# driver.net
KiCad netlist of a schematic drawn in EAGLE
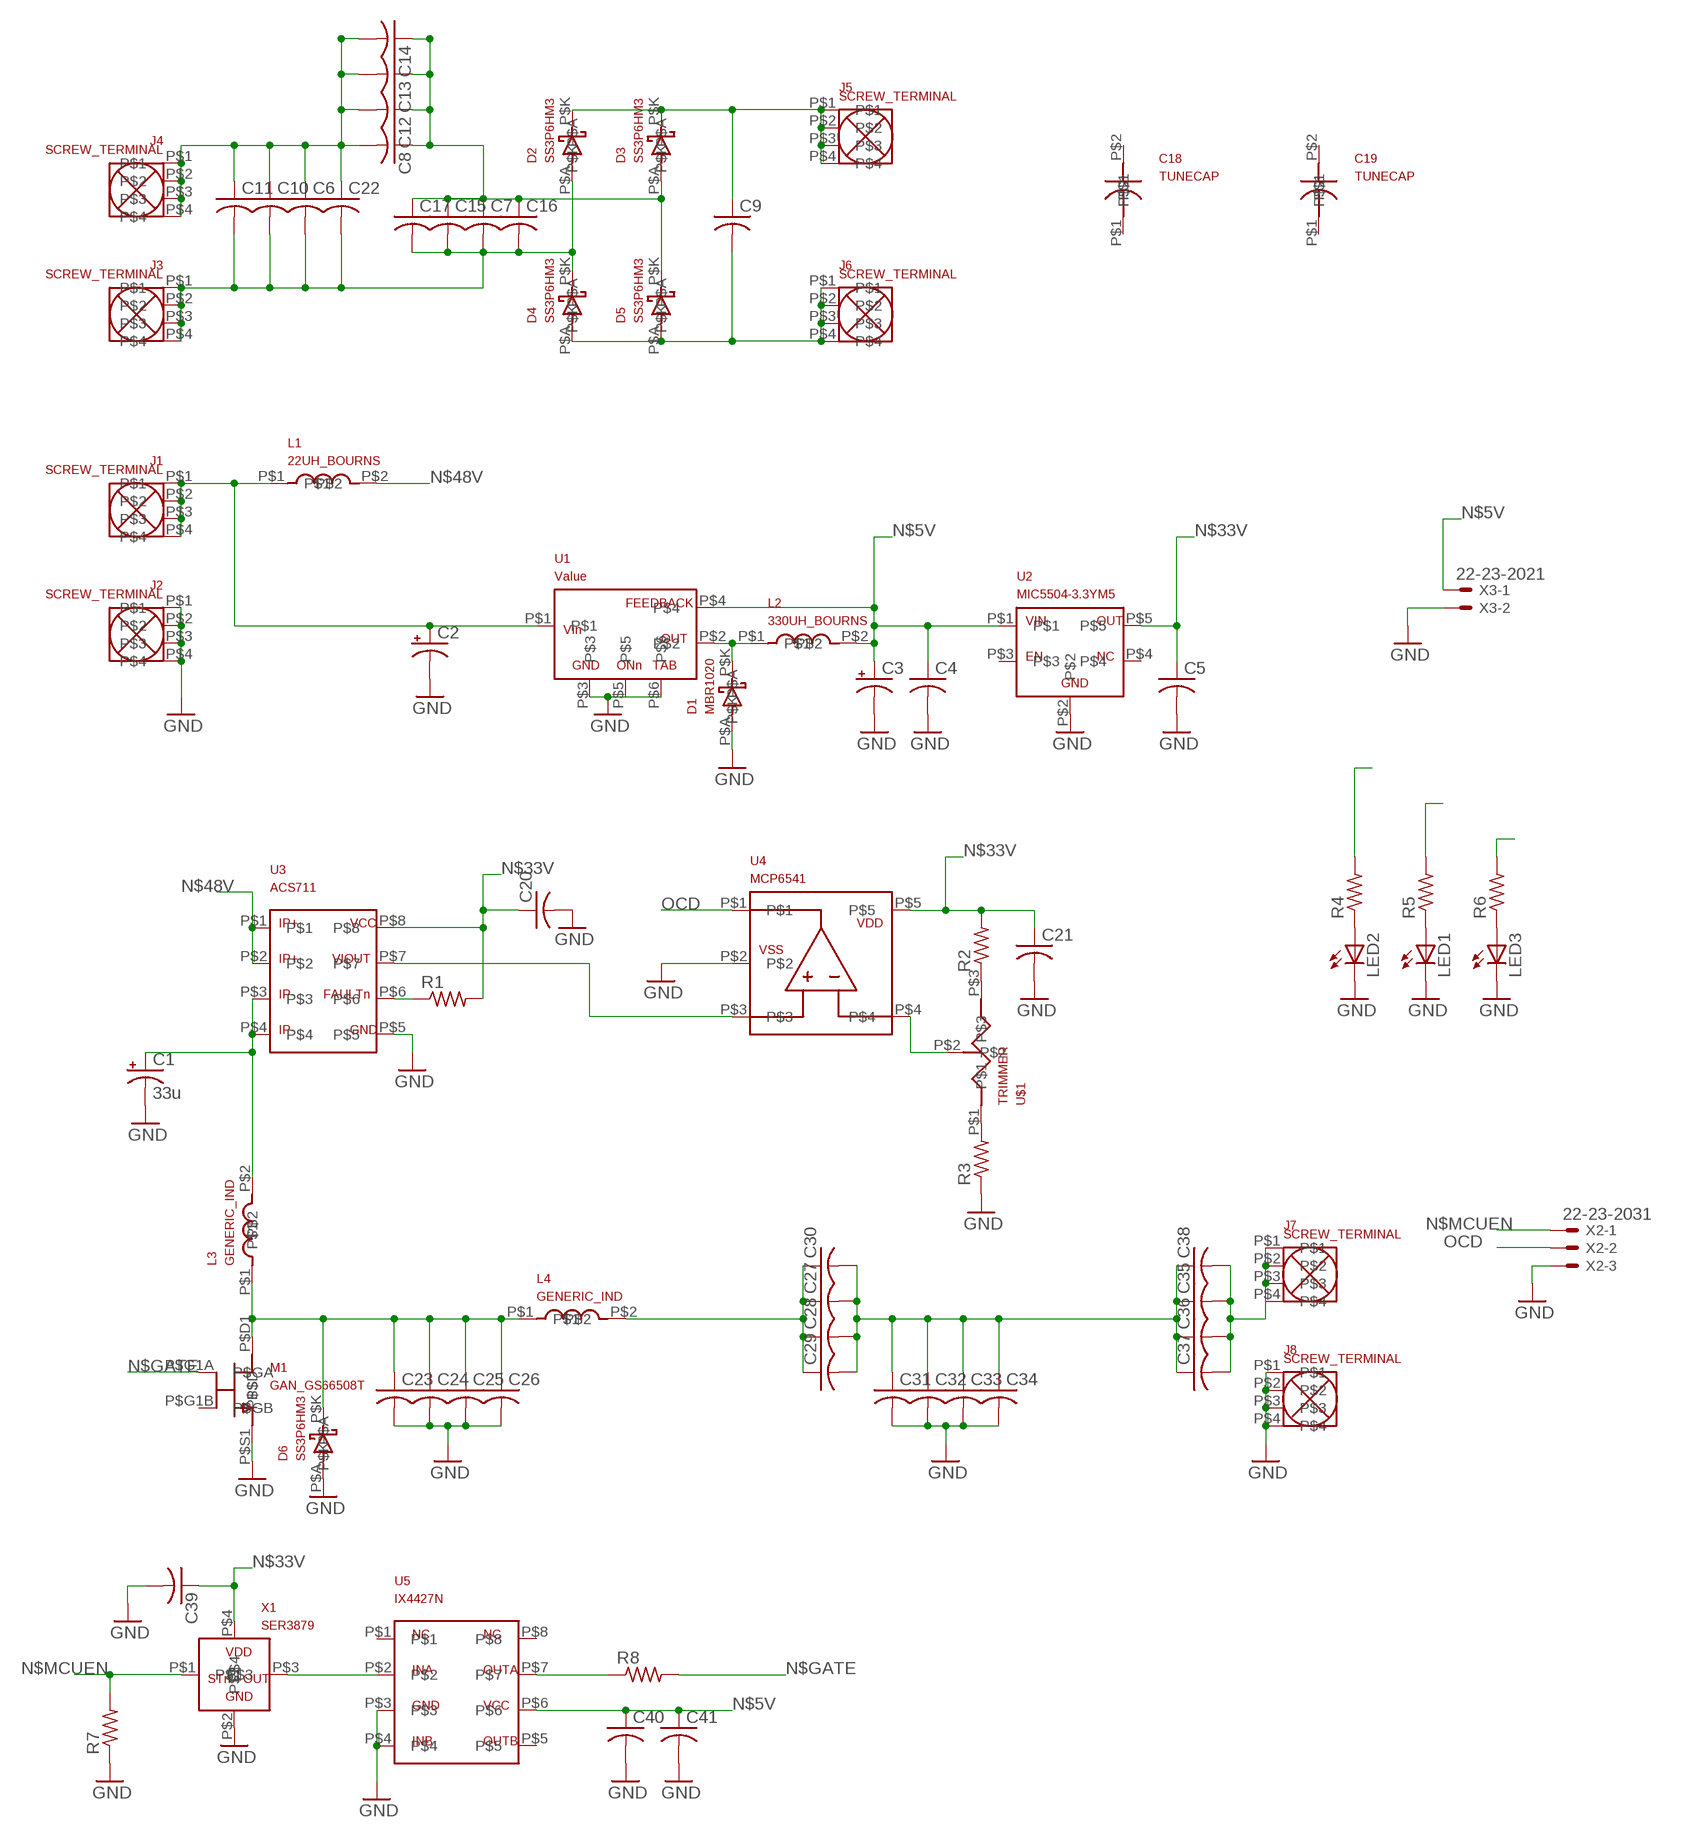
[diagram p0: schematic, sheet 1]

(export (version "E")
  (design (tool "Eeschema 10.0.6"))
  (components
    (comp (ref "C1")
      (value "33u")
      (footprint "eagle-import:140CLH-0810")
      (libsource (lib "eagle-import") (part "CPOL-US140CLH-0810"))
    )
    (comp (ref "C2")
      (value "CPOL-US140CLH-1010")
      (footprint "eagle-import:140CLH-1010")
      (libsource (lib "eagle-import") (part "CPOL-US140CLH-1010"))
    )
    (comp (ref "C3")
      (value "CPOL-US150CLZ-0810")
      (footprint "eagle-import:150CLZ-0810")
      (libsource (lib "eagle-import") (part "CPOL-US150CLZ-0810"))
    )
    (comp (ref "C4")
      (value "C-USC0603K")
      (footprint "eagle-import:C0603K")
      (libsource (lib "eagle-import") (part "C-USC0603K"))
    )
    (comp (ref "C5")
      (value "C-USC0603K")
      (footprint "eagle-import:C0603K")
      (libsource (lib "eagle-import") (part "C-USC0603K"))
    )
    (comp (ref "C6")
      (value "C-USC1206K")
      (footprint "eagle-import:C1206K")
      (libsource (lib "eagle-import") (part "C-USC1206K"))
    )
    (comp (ref "C7")
      (value "C-USC1206K")
      (footprint "eagle-import:C1206K")
      (libsource (lib "eagle-import") (part "C-USC1206K"))
    )
    (comp (ref "C8")
      (value "C-USC1206K")
      (footprint "eagle-import:C1206K")
      (libsource (lib "eagle-import") (part "C-USC1206K"))
    )
    (comp (ref "C9")
      (value "C-USC1206K")
      (footprint "eagle-import:C1206K")
      (libsource (lib "eagle-import") (part "C-USC1206K"))
    )
    (comp (ref "C10")
      (value "C-USC1206K")
      (footprint "eagle-import:C1206K")
      (libsource (lib "eagle-import") (part "C-USC1206K"))
    )
    (comp (ref "C11")
      (value "C-USC1206K")
      (footprint "eagle-import:C1206K")
      (libsource (lib "eagle-import") (part "C-USC1206K"))
    )
    (comp (ref "C12")
      (value "C-USC1206K")
      (footprint "eagle-import:C1206K")
      (libsource (lib "eagle-import") (part "C-USC1206K"))
    )
    (comp (ref "C13")
      (value "C-USC1206K")
      (footprint "eagle-import:C1206K")
      (libsource (lib "eagle-import") (part "C-USC1206K"))
    )
    (comp (ref "C14")
      (value "C-USC1206K")
      (footprint "eagle-import:C1206K")
      (libsource (lib "eagle-import") (part "C-USC1206K"))
    )
    (comp (ref "C15")
      (value "C-USC1206K")
      (footprint "eagle-import:C1206K")
      (libsource (lib "eagle-import") (part "C-USC1206K"))
    )
    (comp (ref "C16")
      (value "C-USC1206K")
      (footprint "eagle-import:C1206K")
      (libsource (lib "eagle-import") (part "C-USC1206K"))
    )
    (comp (ref "C17")
      (value "C-USC1206K")
      (footprint "eagle-import:C1206K")
      (libsource (lib "eagle-import") (part "C-USC1206K"))
    )
    (comp (ref "C18")
      (value "TUNECAP")
      (footprint "eagle-import:CAPTUNE")
      (libsource (lib "eagle-import") (part "TUNECAP"))
    )
    (comp (ref "C19")
      (value "TUNECAP")
      (footprint "eagle-import:CAPTUNE")
      (libsource (lib "eagle-import") (part "TUNECAP"))
    )
    (comp (ref "C20")
      (value "C-USC0603")
      (footprint "eagle-import:C0603")
      (libsource (lib "eagle-import") (part "C-USC0603"))
    )
    (comp (ref "C21")
      (value "C-USC0603K")
      (footprint "eagle-import:C0603K")
      (libsource (lib "eagle-import") (part "C-USC0603K"))
    )
    (comp (ref "C22")
      (value "C-USC1206K")
      (footprint "eagle-import:C1206K")
      (libsource (lib "eagle-import") (part "C-USC1206K"))
    )
    (comp (ref "C23")
      (value "C-USC1206K")
      (footprint "eagle-import:C1206K")
      (libsource (lib "eagle-import") (part "C-USC1206K"))
    )
    (comp (ref "C24")
      (value "C-USC1206K")
      (footprint "eagle-import:C1206K")
      (libsource (lib "eagle-import") (part "C-USC1206K"))
    )
    (comp (ref "C25")
      (value "C-USC1206K")
      (footprint "eagle-import:C1206K")
      (libsource (lib "eagle-import") (part "C-USC1206K"))
    )
    (comp (ref "C26")
      (value "C-USC1206K")
      (footprint "eagle-import:C1206K")
      (libsource (lib "eagle-import") (part "C-USC1206K"))
    )
    (comp (ref "C27")
      (value "C-USC1206K")
      (footprint "eagle-import:C1206K")
      (libsource (lib "eagle-import") (part "C-USC1206K"))
    )
    (comp (ref "C28")
      (value "C-USC1206K")
      (footprint "eagle-import:C1206K")
      (libsource (lib "eagle-import") (part "C-USC1206K"))
    )
    (comp (ref "C29")
      (value "C-USC1206K")
      (footprint "eagle-import:C1206K")
      (libsource (lib "eagle-import") (part "C-USC1206K"))
    )
    (comp (ref "C30")
      (value "C-USC1206K")
      (footprint "eagle-import:C1206K")
      (libsource (lib "eagle-import") (part "C-USC1206K"))
    )
    (comp (ref "C31")
      (value "C-USC1206K")
      (footprint "eagle-import:C1206K")
      (libsource (lib "eagle-import") (part "C-USC1206K"))
    )
    (comp (ref "C32")
      (value "C-USC1206K")
      (footprint "eagle-import:C1206K")
      (libsource (lib "eagle-import") (part "C-USC1206K"))
    )
    (comp (ref "C33")
      (value "C-USC1206K")
      (footprint "eagle-import:C1206K")
      (libsource (lib "eagle-import") (part "C-USC1206K"))
    )
    (comp (ref "C34")
      (value "C-USC1206K")
      (footprint "eagle-import:C1206K")
      (libsource (lib "eagle-import") (part "C-USC1206K"))
    )
    (comp (ref "C35")
      (value "C-USC1206K")
      (footprint "eagle-import:C1206K")
      (libsource (lib "eagle-import") (part "C-USC1206K"))
    )
    (comp (ref "C36")
      (value "C-USC1206K")
      (footprint "eagle-import:C1206K")
      (libsource (lib "eagle-import") (part "C-USC1206K"))
    )
    (comp (ref "C37")
      (value "C-USC1206K")
      (footprint "eagle-import:C1206K")
      (libsource (lib "eagle-import") (part "C-USC1206K"))
    )
    (comp (ref "C38")
      (value "C-USC1206K")
      (footprint "eagle-import:C1206K")
      (libsource (lib "eagle-import") (part "C-USC1206K"))
    )
    (comp (ref "C39")
      (value "C-USC0603K")
      (footprint "eagle-import:C0603K")
      (libsource (lib "eagle-import") (part "C-USC0603K"))
    )
    (comp (ref "C40")
      (value "C-USC0603K")
      (footprint "eagle-import:C0603K")
      (libsource (lib "eagle-import") (part "C-USC0603K"))
    )
    (comp (ref "C41")
      (value "C-USC0603K")
      (footprint "eagle-import:C0603K")
      (libsource (lib "eagle-import") (part "C-USC0603K"))
    )
    (comp (ref "D1")
      (value "MBR1020")
      (footprint "eagle-import:SOD-123")
      (libsource (lib "eagle-import") (part "MBR1020"))
    )
    (comp (ref "D2")
      (value "SS3P6HM3")
      (footprint "eagle-import:D0-220")
      (libsource (lib "eagle-import") (part "SS3P6HM3"))
    )
    (comp (ref "D3")
      (value "SS3P6HM3")
      (footprint "eagle-import:D0-220")
      (libsource (lib "eagle-import") (part "SS3P6HM3"))
    )
    (comp (ref "D4")
      (value "SS3P6HM3")
      (footprint "eagle-import:D0-220")
      (libsource (lib "eagle-import") (part "SS3P6HM3"))
    )
    (comp (ref "D5")
      (value "SS3P6HM3")
      (footprint "eagle-import:D0-220")
      (libsource (lib "eagle-import") (part "SS3P6HM3"))
    )
    (comp (ref "D6")
      (value "SS3P6HM3")
      (footprint "eagle-import:D0-220")
      (libsource (lib "eagle-import") (part "SS3P6HM3"))
    )
    (comp (ref "J1")
      (value "SCREW_TERMINAL")
      (footprint "eagle-import:SCREW_TERMINAL")
      (libsource (lib "eagle-import") (part "SCREW_TERMINAL"))
    )
    (comp (ref "J2")
      (value "SCREW_TERMINAL")
      (footprint "eagle-import:SCREW_TERMINAL")
      (libsource (lib "eagle-import") (part "SCREW_TERMINAL"))
    )
    (comp (ref "J3")
      (value "SCREW_TERMINAL")
      (footprint "eagle-import:SCREW_TERMINAL")
      (libsource (lib "eagle-import") (part "SCREW_TERMINAL"))
    )
    (comp (ref "J4")
      (value "SCREW_TERMINAL")
      (footprint "eagle-import:SCREW_TERMINAL")
      (libsource (lib "eagle-import") (part "SCREW_TERMINAL"))
    )
    (comp (ref "J5")
      (value "SCREW_TERMINAL")
      (footprint "eagle-import:SCREW_TERMINAL")
      (libsource (lib "eagle-import") (part "SCREW_TERMINAL"))
    )
    (comp (ref "J6")
      (value "SCREW_TERMINAL")
      (footprint "eagle-import:SCREW_TERMINAL")
      (libsource (lib "eagle-import") (part "SCREW_TERMINAL"))
    )
    (comp (ref "J7")
      (value "SCREW_TERMINAL")
      (footprint "eagle-import:SCREW_TERMINAL")
      (libsource (lib "eagle-import") (part "SCREW_TERMINAL"))
    )
    (comp (ref "J8")
      (value "SCREW_TERMINAL")
      (footprint "eagle-import:SCREW_TERMINAL")
      (libsource (lib "eagle-import") (part "SCREW_TERMINAL"))
    )
    (comp (ref "L1")
      (value "22UH_BOURNS")
      (footprint "eagle-import:492MIL_IND")
      (libsource (lib "eagle-import") (part "22UH_BOURNS"))
    )
    (comp (ref "L2")
      (value "330UH_BOURNS")
      (footprint "eagle-import:330U_IND")
      (libsource (lib "eagle-import") (part "330UH_BOURNS"))
    )
    (comp (ref "L3")
      (value "GENERIC_IND")
      (footprint "eagle-import:GENERIC_IND")
      (libsource (lib "eagle-import") (part "GENERIC_IND"))
    )
    (comp (ref "L4")
      (value "GENERIC_IND")
      (footprint "eagle-import:GENERIC_IND")
      (libsource (lib "eagle-import") (part "GENERIC_IND"))
    )
    (comp (ref "LED1")
      (value "LEDCHIPLED_0805")
      (footprint "eagle-import:CHIPLED_0805")
      (libsource (lib "eagle-import") (part "LEDCHIPLED_0805"))
    )
    (comp (ref "LED2")
      (value "LEDCHIPLED_0805")
      (footprint "eagle-import:CHIPLED_0805")
      (libsource (lib "eagle-import") (part "LEDCHIPLED_0805"))
    )
    (comp (ref "LED3")
      (value "LEDCHIPLED_0805")
      (footprint "eagle-import:CHIPLED_0805")
      (libsource (lib "eagle-import") (part "LEDCHIPLED_0805"))
    )
    (comp (ref "M1")
      (value "GAN_GS66508T")
      (footprint "eagle-import:GAN_GS66508T")
      (libsource (lib "eagle-import") (part "GAN_GS66508T"))
    )
    (comp (ref "R1")
      (value "R-US_R0603")
      (footprint "eagle-import:R0603")
      (libsource (lib "eagle-import") (part "R-US_R0603"))
    )
    (comp (ref "R2")
      (value "R-US_R0603")
      (footprint "eagle-import:R0603")
      (libsource (lib "eagle-import") (part "R-US_R0603"))
    )
    (comp (ref "R3")
      (value "R-US_R0603")
      (footprint "eagle-import:R0603")
      (libsource (lib "eagle-import") (part "R-US_R0603"))
    )
    (comp (ref "R4")
      (value "R-US_R0603")
      (footprint "eagle-import:R0603")
      (libsource (lib "eagle-import") (part "R-US_R0603"))
    )
    (comp (ref "R5")
      (value "R-US_R0603")
      (footprint "eagle-import:R0603")
      (libsource (lib "eagle-import") (part "R-US_R0603"))
    )
    (comp (ref "R6")
      (value "R-US_R0603")
      (footprint "eagle-import:R0603")
      (libsource (lib "eagle-import") (part "R-US_R0603"))
    )
    (comp (ref "R7")
      (value "R-US_R0603")
      (footprint "eagle-import:R0603")
      (libsource (lib "eagle-import") (part "R-US_R0603"))
    )
    (comp (ref "R8")
      (value "R-US_R0603")
      (footprint "eagle-import:R0603")
      (libsource (lib "eagle-import") (part "R-US_R0603"))
    )
    (comp (ref "U$1")
      (value "TRIMMER")
      (footprint "eagle-import:TRIMMER")
      (libsource (lib "eagle-import") (part "TRIMMER"))
    )
    (comp (ref "U1")
      (value "TL2575HV")
      (footprint "eagle-import:TL2575HV")
      (libsource (lib "eagle-import") (part "TL2575HV"))
    )
    (comp (ref "U2")
      (value "MIC5504-3.3YM5")
      (footprint "eagle-import:MIC5504-3.3YM5")
      (libsource (lib "eagle-import") (part "MIC5504-3.3YM5"))
    )
    (comp (ref "U3")
      (value "ACS711")
      (footprint "eagle-import:IX4427N")
      (libsource (lib "eagle-import") (part "ACS711"))
    )
    (comp (ref "U4")
      (value "MCP6541")
      (footprint "eagle-import:SC-70-5")
      (libsource (lib "eagle-import") (part "MCP6541"))
    )
    (comp (ref "U5")
      (value "IX4427N")
      (footprint "eagle-import:IX4427N")
      (libsource (lib "eagle-import") (part "IX4427N"))
    )
    (comp (ref "X1")
      (value "SER3879")
      (footprint "eagle-import:SER3879-ND")
      (libsource (lib "eagle-import") (part "SER3879"))
    )
    (comp (ref "X2")
      (value "22-23-2031")
      (footprint "eagle-import:22-23-2031")
      (fields (field (name "MF") "MOLEX"))
      (libsource (lib "eagle-import") (part "22-23-2031"))
    )
    (comp (ref "X3")
      (value "22-23-2021")
      (footprint "eagle-import:22-23-2021")
      (fields (field (name "MF") "MOLEX"))
      (libsource (lib "eagle-import") (part "22-23-2021"))
    )
  )
  (nets
    (net (code "1") (name "/N$5V") (class "Default")
      (node (ref "C3") (pin "+") (pinfunction "+_+") (pintype "passive"))
      (node (ref "C4") (pin "1") (pinfunction "1_1") (pintype "passive"))
      (node (ref "C40") (pin "1") (pinfunction "1_1") (pintype "passive"))
      (node (ref "C41") (pin "1") (pinfunction "1_1") (pintype "passive"))
      (node (ref "L2") (pin "P$2") (pinfunction "P$2_P$2") (pintype "bidirectional"))
      (node (ref "R4") (pin "2") (pinfunction "2_2") (pintype "passive"))
      (node (ref "U1") (pin "P$4") (pinfunction "P$4_P$4") (pintype "bidirectional"))
      (node (ref "U2") (pin "P$1") (pinfunction "P$1_P$1") (pintype "bidirectional"))
      (node (ref "U5") (pin "P$6") (pinfunction "P$6_P$6") (pintype "bidirectional"))
      (node (ref "X3") (pin "1") (pinfunction "S_1") (pintype "passive"))
    )
    (net (code "2") (name "/N$33V") (class "Default")
      (node (ref "C20") (pin "1") (pinfunction "1_1") (pintype "passive"))
      (node (ref "C21") (pin "1") (pinfunction "1_1") (pintype "passive"))
      (node (ref "C39") (pin "1") (pinfunction "1_1") (pintype "passive"))
      (node (ref "C5") (pin "1") (pinfunction "1_1") (pintype "passive"))
      (node (ref "R1") (pin "2") (pinfunction "2_2") (pintype "passive"))
      (node (ref "R2") (pin "2") (pinfunction "2_2") (pintype "passive"))
      (node (ref "U2") (pin "P$5") (pinfunction "P$5_P$5") (pintype "bidirectional"))
      (node (ref "U3") (pin "P$8") (pinfunction "P$8_P$8") (pintype "bidirectional"))
      (node (ref "U4") (pin "P$5") (pinfunction "P$5_P$5") (pintype "bidirectional"))
      (node (ref "X1") (pin "P$4") (pinfunction "P$4_P$4") (pintype "bidirectional"))
    )
    (net (code "3") (name "/N$48V") (class "Default")
      (node (ref "L1") (pin "P$2") (pinfunction "P$2_P$2") (pintype "bidirectional"))
      (node (ref "U3") (pin "P$1") (pinfunction "P$1_P$1") (pintype "bidirectional"))
      (node (ref "U3") (pin "P$2") (pinfunction "P$2_P$2") (pintype "bidirectional"))
    )
    (net (code "4") (name "/N$GATE") (class "Default")
      (node (ref "M1") (pin "P$G1A") (pinfunction "P$GA_P$G1A") (pintype "bidirectional"))
      (node (ref "R8") (pin "2") (pinfunction "2_2") (pintype "passive"))
    )
    (net (code "5") (name "/N$MCUEN") (class "Default")
      (node (ref "R6") (pin "2") (pinfunction "2_2") (pintype "passive"))
      (node (ref "R7") (pin "2") (pinfunction "2_2") (pintype "passive"))
      (node (ref "X1") (pin "P$1") (pinfunction "P$1_P$1") (pintype "bidirectional"))
      (node (ref "X2") (pin "1") (pinfunction "S_1") (pintype "passive"))
    )
    (net (code "6") (name "/OCD") (class "Default")
      (node (ref "R5") (pin "2") (pinfunction "2_2") (pintype "passive"))
      (node (ref "U4") (pin "P$1") (pinfunction "P$1_P$1") (pintype "bidirectional"))
      (node (ref "X2") (pin "2") (pinfunction "S_2") (pintype "passive"))
    )
    (net (code "7") (name "GND") (class "Default")
      (node (ref "C1") (pin "-") (pinfunction "-_-") (pintype "passive"))
      (node (ref "C2") (pin "-") (pinfunction "-_-") (pintype "passive"))
      (node (ref "C20") (pin "2") (pinfunction "2_2") (pintype "passive"))
      (node (ref "C21") (pin "2") (pinfunction "2_2") (pintype "passive"))
      (node (ref "C23") (pin "2") (pinfunction "2_2") (pintype "passive"))
      (node (ref "C24") (pin "2") (pinfunction "2_2") (pintype "passive"))
      (node (ref "C25") (pin "2") (pinfunction "2_2") (pintype "passive"))
      (node (ref "C26") (pin "2") (pinfunction "2_2") (pintype "passive"))
      (node (ref "C3") (pin "-") (pinfunction "-_-") (pintype "passive"))
      (node (ref "C31") (pin "2") (pinfunction "2_2") (pintype "passive"))
      (node (ref "C32") (pin "2") (pinfunction "2_2") (pintype "passive"))
      (node (ref "C33") (pin "2") (pinfunction "2_2") (pintype "passive"))
      (node (ref "C34") (pin "2") (pinfunction "2_2") (pintype "passive"))
      (node (ref "C39") (pin "2") (pinfunction "2_2") (pintype "passive"))
      (node (ref "C4") (pin "2") (pinfunction "2_2") (pintype "passive"))
      (node (ref "C40") (pin "2") (pinfunction "2_2") (pintype "passive"))
      (node (ref "C41") (pin "2") (pinfunction "2_2") (pintype "passive"))
      (node (ref "C5") (pin "2") (pinfunction "2_2") (pintype "passive"))
      (node (ref "D1") (pin "P$A") (pinfunction "P$A_P$A") (pintype "bidirectional"))
      (node (ref "D6") (pin "P$A") (pinfunction "P$A_P$A") (pintype "bidirectional"))
      (node (ref "J2") (pin "P$1") (pinfunction "P$1_P$1") (pintype "bidirectional"))
      (node (ref "J2") (pin "P$2") (pinfunction "P$2_P$2") (pintype "bidirectional"))
      (node (ref "J2") (pin "P$3") (pinfunction "P$3_P$3") (pintype "bidirectional"))
      (node (ref "J2") (pin "P$4") (pinfunction "P$4_P$4") (pintype "bidirectional"))
      (node (ref "J8") (pin "P$1") (pinfunction "P$1_P$1") (pintype "bidirectional"))
      (node (ref "J8") (pin "P$2") (pinfunction "P$2_P$2") (pintype "bidirectional"))
      (node (ref "J8") (pin "P$3") (pinfunction "P$3_P$3") (pintype "bidirectional"))
      (node (ref "J8") (pin "P$4") (pinfunction "P$4_P$4") (pintype "bidirectional"))
      (node (ref "LED1") (pin "C") (pinfunction "C_C") (pintype "passive"))
      (node (ref "LED2") (pin "C") (pinfunction "C_C") (pintype "passive"))
      (node (ref "LED3") (pin "C") (pinfunction "C_C") (pintype "passive"))
      (node (ref "M1") (pin "P$S1") (pinfunction "P$S_P$S1") (pintype "bidirectional"))
      (node (ref "R3") (pin "1") (pinfunction "1_1") (pintype "passive"))
      (node (ref "R7") (pin "1") (pinfunction "1_1") (pintype "passive"))
      (node (ref "U1") (pin "P$3") (pinfunction "P$3_P$3") (pintype "bidirectional"))
      (node (ref "U1") (pin "P$5") (pinfunction "P$5_P$5") (pintype "bidirectional"))
      (node (ref "U1") (pin "P$6") (pinfunction "P$6_P$6") (pintype "bidirectional"))
      (node (ref "U2") (pin "P$2") (pinfunction "P$2_P$2") (pintype "bidirectional"))
      (node (ref "U3") (pin "P$5") (pinfunction "P$5_P$5") (pintype "bidirectional"))
      (node (ref "U4") (pin "P$2") (pinfunction "P$2_P$2") (pintype "bidirectional"))
      (node (ref "U5") (pin "P$3") (pinfunction "P$3_P$3") (pintype "bidirectional"))
      (node (ref "U5") (pin "P$4") (pinfunction "P$4_P$4") (pintype "bidirectional"))
      (node (ref "X1") (pin "P$2") (pinfunction "P$2_P$2") (pintype "bidirectional"))
      (node (ref "X2") (pin "3") (pinfunction "S_3") (pintype "passive"))
      (node (ref "X3") (pin "2") (pinfunction "S_2") (pintype "passive"))
    )
    (net (code "8") (name "Net-(C1-Pad+)") (class "Default")
      (node (ref "C1") (pin "+") (pinfunction "+_+") (pintype "passive"))
      (node (ref "L3") (pin "P$2") (pinfunction "P$2_P$2") (pintype "bidirectional"))
      (node (ref "U3") (pin "P$3") (pinfunction "P$3_P$3") (pintype "bidirectional"))
      (node (ref "U3") (pin "P$4") (pinfunction "P$4_P$4") (pintype "bidirectional"))
    )
    (net (code "9") (name "Net-(C2-Pad+)") (class "Default")
      (node (ref "C2") (pin "+") (pinfunction "+_+") (pintype "passive"))
      (node (ref "J1") (pin "P$1") (pinfunction "P$1_P$1") (pintype "bidirectional"))
      (node (ref "J1") (pin "P$2") (pinfunction "P$2_P$2") (pintype "bidirectional"))
      (node (ref "J1") (pin "P$3") (pinfunction "P$3_P$3") (pintype "bidirectional"))
      (node (ref "J1") (pin "P$4") (pinfunction "P$4_P$4") (pintype "bidirectional"))
      (node (ref "L1") (pin "P$1") (pinfunction "P$1_P$1") (pintype "bidirectional"))
      (node (ref "U1") (pin "P$1") (pinfunction "P$1_P$1") (pintype "bidirectional"))
    )
    (net (code "10") (name "Net-(C9-Pad1)") (class "Default")
      (node (ref "C9") (pin "1") (pinfunction "1_1") (pintype "passive"))
      (node (ref "D2") (pin "P$K") (pinfunction "P$K_P$K") (pintype "bidirectional"))
      (node (ref "D3") (pin "P$K") (pinfunction "P$K_P$K") (pintype "bidirectional"))
      (node (ref "J5") (pin "P$1") (pinfunction "P$1_P$1") (pintype "bidirectional"))
      (node (ref "J5") (pin "P$2") (pinfunction "P$2_P$2") (pintype "bidirectional"))
      (node (ref "J5") (pin "P$3") (pinfunction "P$3_P$3") (pintype "bidirectional"))
      (node (ref "J5") (pin "P$4") (pinfunction "P$4_P$4") (pintype "bidirectional"))
    )
    (net (code "11") (name "Net-(C9-Pad2)") (class "Default")
      (node (ref "C9") (pin "2") (pinfunction "2_2") (pintype "passive"))
      (node (ref "D4") (pin "P$A") (pinfunction "P$A_P$A") (pintype "bidirectional"))
      (node (ref "D5") (pin "P$A") (pinfunction "P$A_P$A") (pintype "bidirectional"))
      (node (ref "J6") (pin "P$1") (pinfunction "P$1_P$1") (pintype "bidirectional"))
      (node (ref "J6") (pin "P$2") (pinfunction "P$2_P$2") (pintype "bidirectional"))
      (node (ref "J6") (pin "P$3") (pinfunction "P$3_P$3") (pintype "bidirectional"))
      (node (ref "J6") (pin "P$4") (pinfunction "P$4_P$4") (pintype "bidirectional"))
    )
    (net (code "12") (name "Net-(C10-Pad1)") (class "Default")
      (node (ref "C10") (pin "1") (pinfunction "1_1") (pintype "passive"))
      (node (ref "C11") (pin "1") (pinfunction "1_1") (pintype "passive"))
      (node (ref "C12") (pin "2") (pinfunction "2_2") (pintype "passive"))
      (node (ref "C13") (pin "2") (pinfunction "2_2") (pintype "passive"))
      (node (ref "C14") (pin "2") (pinfunction "2_2") (pintype "passive"))
      (node (ref "C22") (pin "1") (pinfunction "1_1") (pintype "passive"))
      (node (ref "C6") (pin "1") (pinfunction "1_1") (pintype "passive"))
      (node (ref "C8") (pin "2") (pinfunction "2_2") (pintype "passive"))
      (node (ref "J4") (pin "P$1") (pinfunction "P$1_P$1") (pintype "bidirectional"))
      (node (ref "J4") (pin "P$2") (pinfunction "P$2_P$2") (pintype "bidirectional"))
      (node (ref "J4") (pin "P$3") (pinfunction "P$3_P$3") (pintype "bidirectional"))
      (node (ref "J4") (pin "P$4") (pinfunction "P$4_P$4") (pintype "bidirectional"))
    )
    (net (code "13") (name "Net-(C10-Pad2)") (class "Default")
      (node (ref "C10") (pin "2") (pinfunction "2_2") (pintype "passive"))
      (node (ref "C11") (pin "2") (pinfunction "2_2") (pintype "passive"))
      (node (ref "C15") (pin "2") (pinfunction "2_2") (pintype "passive"))
      (node (ref "C16") (pin "2") (pinfunction "2_2") (pintype "passive"))
      (node (ref "C17") (pin "2") (pinfunction "2_2") (pintype "passive"))
      (node (ref "C22") (pin "2") (pinfunction "2_2") (pintype "passive"))
      (node (ref "C6") (pin "2") (pinfunction "2_2") (pintype "passive"))
      (node (ref "C7") (pin "2") (pinfunction "2_2") (pintype "passive"))
      (node (ref "D2") (pin "P$A") (pinfunction "P$A_P$A") (pintype "bidirectional"))
      (node (ref "D4") (pin "P$K") (pinfunction "P$K_P$K") (pintype "bidirectional"))
      (node (ref "J3") (pin "P$1") (pinfunction "P$1_P$1") (pintype "bidirectional"))
      (node (ref "J3") (pin "P$2") (pinfunction "P$2_P$2") (pintype "bidirectional"))
      (node (ref "J3") (pin "P$3") (pinfunction "P$3_P$3") (pintype "bidirectional"))
      (node (ref "J3") (pin "P$4") (pinfunction "P$4_P$4") (pintype "bidirectional"))
    )
    (net (code "14") (name "Net-(C12-Pad1)") (class "Default")
      (node (ref "C12") (pin "1") (pinfunction "1_1") (pintype "passive"))
      (node (ref "C13") (pin "1") (pinfunction "1_1") (pintype "passive"))
      (node (ref "C14") (pin "1") (pinfunction "1_1") (pintype "passive"))
      (node (ref "C15") (pin "1") (pinfunction "1_1") (pintype "passive"))
      (node (ref "C16") (pin "1") (pinfunction "1_1") (pintype "passive"))
      (node (ref "C17") (pin "1") (pinfunction "1_1") (pintype "passive"))
      (node (ref "C7") (pin "1") (pinfunction "1_1") (pintype "passive"))
      (node (ref "C8") (pin "1") (pinfunction "1_1") (pintype "passive"))
      (node (ref "D3") (pin "P$A") (pinfunction "P$A_P$A") (pintype "bidirectional"))
      (node (ref "D5") (pin "P$K") (pinfunction "P$K_P$K") (pintype "bidirectional"))
    )
    (net (code "15") (name "Net-(C27-Pad1)") (class "Default")
      (node (ref "C27") (pin "1") (pinfunction "1_1") (pintype "passive"))
      (node (ref "C28") (pin "1") (pinfunction "1_1") (pintype "passive"))
      (node (ref "C29") (pin "1") (pinfunction "1_1") (pintype "passive"))
      (node (ref "C30") (pin "1") (pinfunction "1_1") (pintype "passive"))
      (node (ref "L4") (pin "P$2") (pinfunction "P$2_P$2") (pintype "bidirectional"))
    )
    (net (code "16") (name "Net-(C27-Pad2)") (class "Default")
      (node (ref "C27") (pin "2") (pinfunction "2_2") (pintype "passive"))
      (node (ref "C28") (pin "2") (pinfunction "2_2") (pintype "passive"))
      (node (ref "C29") (pin "2") (pinfunction "2_2") (pintype "passive"))
      (node (ref "C30") (pin "2") (pinfunction "2_2") (pintype "passive"))
      (node (ref "C31") (pin "1") (pinfunction "1_1") (pintype "passive"))
      (node (ref "C32") (pin "1") (pinfunction "1_1") (pintype "passive"))
      (node (ref "C33") (pin "1") (pinfunction "1_1") (pintype "passive"))
      (node (ref "C34") (pin "1") (pinfunction "1_1") (pintype "passive"))
      (node (ref "C35") (pin "1") (pinfunction "1_1") (pintype "passive"))
      (node (ref "C36") (pin "1") (pinfunction "1_1") (pintype "passive"))
      (node (ref "C37") (pin "1") (pinfunction "1_1") (pintype "passive"))
      (node (ref "C38") (pin "1") (pinfunction "1_1") (pintype "passive"))
    )
    (net (code "17") (name "Net-(C35-Pad2)") (class "Default")
      (node (ref "C35") (pin "2") (pinfunction "2_2") (pintype "passive"))
      (node (ref "C36") (pin "2") (pinfunction "2_2") (pintype "passive"))
      (node (ref "C37") (pin "2") (pinfunction "2_2") (pintype "passive"))
      (node (ref "C38") (pin "2") (pinfunction "2_2") (pintype "passive"))
      (node (ref "J7") (pin "P$1") (pinfunction "P$1_P$1") (pintype "bidirectional"))
      (node (ref "J7") (pin "P$2") (pinfunction "P$2_P$2") (pintype "bidirectional"))
      (node (ref "J7") (pin "P$3") (pinfunction "P$3_P$3") (pintype "bidirectional"))
      (node (ref "J7") (pin "P$4") (pinfunction "P$4_P$4") (pintype "bidirectional"))
    )
    (net (code "18") (name "Net-(D1-PadP$K)") (class "Default")
      (node (ref "D1") (pin "P$K") (pinfunction "P$K_P$K") (pintype "bidirectional"))
      (node (ref "L2") (pin "P$1") (pinfunction "P$1_P$1") (pintype "bidirectional"))
      (node (ref "U1") (pin "P$2") (pinfunction "P$2_P$2") (pintype "bidirectional"))
    )
    (net (code "19") (name "Net-(LED1-PadA)") (class "Default")
      (node (ref "LED1") (pin "A") (pinfunction "A_A") (pintype "passive"))
      (node (ref "R5") (pin "1") (pinfunction "1_1") (pintype "passive"))
    )
    (net (code "20") (name "Net-(LED2-PadA)") (class "Default")
      (node (ref "LED2") (pin "A") (pinfunction "A_A") (pintype "passive"))
      (node (ref "R4") (pin "1") (pinfunction "1_1") (pintype "passive"))
    )
    (net (code "21") (name "Net-(LED3-PadA)") (class "Default")
      (node (ref "LED3") (pin "A") (pinfunction "A_A") (pintype "passive"))
      (node (ref "R6") (pin "1") (pinfunction "1_1") (pintype "passive"))
    )
    (net (code "22") (name "Net-(M1-P$D)") (class "Default")
      (node (ref "C23") (pin "1") (pinfunction "1_1") (pintype "passive"))
      (node (ref "C24") (pin "1") (pinfunction "1_1") (pintype "passive"))
      (node (ref "C25") (pin "1") (pinfunction "1_1") (pintype "passive"))
      (node (ref "C26") (pin "1") (pinfunction "1_1") (pintype "passive"))
      (node (ref "D6") (pin "P$K") (pinfunction "P$K_P$K") (pintype "bidirectional"))
      (node (ref "L3") (pin "P$1") (pinfunction "P$1_P$1") (pintype "bidirectional"))
      (node (ref "L4") (pin "P$1") (pinfunction "P$1_P$1") (pintype "bidirectional"))
      (node (ref "M1") (pin "P$D1") (pinfunction "P$D_P$D1") (pintype "bidirectional"))
    )
    (net (code "23") (name "Net-(R1-Pad1)") (class "Default")
      (node (ref "R1") (pin "1") (pinfunction "1_1") (pintype "passive"))
      (node (ref "U3") (pin "P$6") (pinfunction "P$6_P$6") (pintype "bidirectional"))
    )
    (net (code "24") (name "Net-(R2-Pad1)") (class "Default")
      (node (ref "R2") (pin "1") (pinfunction "1_1") (pintype "passive"))
      (node (ref "U$1") (pin "P$3") (pinfunction "P$3_P$3") (pintype "bidirectional"))
    )
    (net (code "25") (name "Net-(R3-Pad2)") (class "Default")
      (node (ref "R3") (pin "2") (pinfunction "2_2") (pintype "passive"))
      (node (ref "U$1") (pin "P$1") (pinfunction "P$1_P$1") (pintype "bidirectional"))
    )
    (net (code "26") (name "Net-(R8-Pad1)") (class "Default")
      (node (ref "R8") (pin "1") (pinfunction "1_1") (pintype "passive"))
      (node (ref "U5") (pin "P$7") (pinfunction "P$7_P$7") (pintype "bidirectional"))
    )
    (net (code "27") (name "Net-(U$1-PadP$2)") (class "Default")
      (node (ref "U$1") (pin "P$2") (pinfunction "P$2_P$2") (pintype "bidirectional"))
      (node (ref "U4") (pin "P$4") (pinfunction "P$4_P$4") (pintype "bidirectional"))
    )
    (net (code "28") (name "Net-(U3-PadP$7)") (class "Default")
      (node (ref "U3") (pin "P$7") (pinfunction "P$7_P$7") (pintype "bidirectional"))
      (node (ref "U4") (pin "P$3") (pinfunction "P$3_P$3") (pintype "bidirectional"))
    )
    (net (code "29") (name "Net-(U5-PadP$2)") (class "Default")
      (node (ref "U5") (pin "P$2") (pinfunction "P$2_P$2") (pintype "bidirectional"))
      (node (ref "X1") (pin "P$3") (pinfunction "P$3_P$3") (pintype "bidirectional"))
    )
    (net (code "30") (name "unconnected-(C18-PadP$1)") (class "Default")
      (node (ref "C18") (pin "P$1") (pinfunction "P$1_P$1") (pintype "bidirectional"))
    )
    (net (code "31") (name "unconnected-(C18-PadP$2)") (class "Default")
      (node (ref "C18") (pin "P$2") (pinfunction "P$2_P$2") (pintype "bidirectional"))
    )
    (net (code "32") (name "unconnected-(C19-PadP$1)") (class "Default")
      (node (ref "C19") (pin "P$1") (pinfunction "P$1_P$1") (pintype "bidirectional"))
    )
    (net (code "33") (name "unconnected-(C19-PadP$2)") (class "Default")
      (node (ref "C19") (pin "P$2") (pinfunction "P$2_P$2") (pintype "bidirectional"))
    )
    (net (code "34") (name "unconnected-(M1-P$GB-PadP$G1B)") (class "Default")
      (node (ref "M1") (pin "P$G1B") (pinfunction "P$GB_P$G1B") (pintype "bidirectional"))
    )
    (net (code "35") (name "unconnected-(U2-PadP$3)") (class "Default")
      (node (ref "U2") (pin "P$3") (pinfunction "P$3_P$3") (pintype "bidirectional"))
    )
    (net (code "36") (name "unconnected-(U2-PadP$4)") (class "Default")
      (node (ref "U2") (pin "P$4") (pinfunction "P$4_P$4") (pintype "bidirectional"))
    )
    (net (code "37") (name "unconnected-(U5-PadP$1)") (class "Default")
      (node (ref "U5") (pin "P$1") (pinfunction "P$1_P$1") (pintype "bidirectional"))
    )
    (net (code "38") (name "unconnected-(U5-PadP$5)") (class "Default")
      (node (ref "U5") (pin "P$5") (pinfunction "P$5_P$5") (pintype "bidirectional"))
    )
    (net (code "39") (name "unconnected-(U5-PadP$8)") (class "Default")
      (node (ref "U5") (pin "P$8") (pinfunction "P$8_P$8") (pintype "bidirectional"))
    )
  )
)
